# can-SN65HVD233.net
KiCad netlist of a schematic drawn in Altium Designer
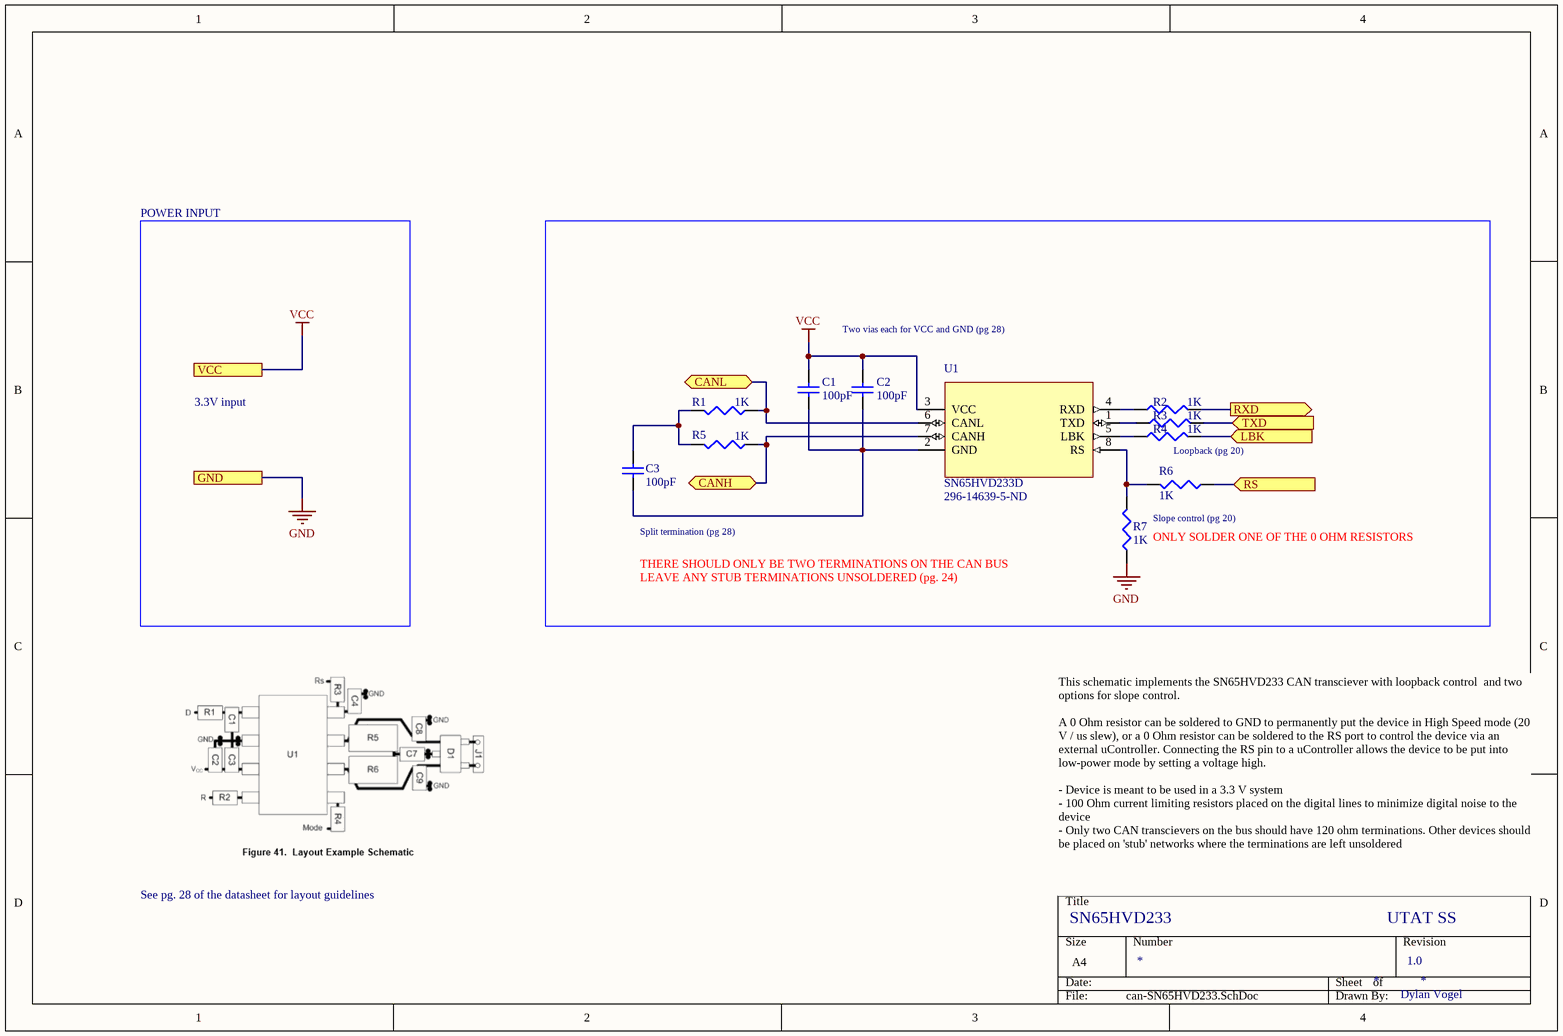
[diagram p0: can-SN65HVD233.SchDoc]

(export (version "E")
  (design (tool "Eeschema 10.0.6"))
  (components
    (comp (ref "C1")
      (value "100pF")
      (footprint "C1206")
      (description "Capacitor (Semiconductor SIM Model)")
      (fields (field (name "Comment") "Cap Semi") (field (name "PUBLISHER") "Altium Limited"))
      (libsource (lib "Miscellaneous Devices") (part "Cap Semi"))
    )
    (comp (ref "C2")
      (value "100pF")
      (footprint "C1206")
      (description "Capacitor (Semiconductor SIM Model)")
      (fields (field (name "Comment") "Cap Semi") (field (name "PUBLISHER") "Altium Limited"))
      (libsource (lib "Miscellaneous Devices") (part "Cap Semi"))
    )
    (comp (ref "C3")
      (value "100pF")
      (footprint "C1206")
      (description "Capacitor (Semiconductor SIM Model)")
      (fields (field (name "Comment") "Cap Semi") (field (name "PUBLISHER") "Altium Limited"))
      (libsource (lib "Miscellaneous Devices") (part "Cap Semi"))
    )
    (comp (ref "R1")
      (value "1K")
      (footprint "J1-0603")
      (description "Resistor")
      (fields (field (name "Comment") "Res3") (field (name "PUBLISHER") "Altium Limited"))
      (libsource (lib "Miscellaneous Devices") (part "Res3"))
    )
    (comp (ref "R2")
      (value "1K")
      (footprint "J1-0603")
      (description "Resistor")
      (fields (field (name "Comment") "Res3") (field (name "PUBLISHER") "Altium Limited"))
      (libsource (lib "Miscellaneous Devices") (part "Res3"))
    )
    (comp (ref "R3")
      (value "1K")
      (footprint "J1-0603")
      (description "Resistor")
      (fields (field (name "Comment") "Res3") (field (name "PUBLISHER") "Altium Limited"))
      (libsource (lib "Miscellaneous Devices") (part "Res3"))
    )
    (comp (ref "R4")
      (value "1K")
      (footprint "J1-0603")
      (description "Resistor")
      (fields (field (name "Comment") "Res3") (field (name "PUBLISHER") "Altium Limited"))
      (libsource (lib "Miscellaneous Devices") (part "Res3"))
    )
    (comp (ref "R5")
      (value "1K")
      (footprint "J1-0603")
      (description "Resistor")
      (fields (field (name "Comment") "Res3") (field (name "PUBLISHER") "Altium Limited"))
      (libsource (lib "Miscellaneous Devices") (part "Res3"))
    )
    (comp (ref "R6")
      (value "1K")
      (footprint "J1-0603")
      (description "Resistor")
      (fields (field (name "Comment") "Res3") (field (name "PUBLISHER") "Altium Limited"))
      (libsource (lib "Miscellaneous Devices") (part "Res3"))
    )
    (comp (ref "R7")
      (value "1K")
      (footprint "J1-0603")
      (description "Resistor")
      (fields (field (name "Comment") "Res3") (field (name "PUBLISHER") "Altium Limited"))
      (libsource (lib "Miscellaneous Devices") (part "Res3"))
    )
    (comp (ref "U1")
      (value "SN65HVD233D")
      (footprint "SOIC127P500X600-8N")
      (description "3.3V CAN Transceiver with Standby Mode, Loop-back 8-SOIC -40 to 125")
      (fields
        (field (name "MF") "Texas Instruments")
        (field (name "SUPPLIER PART NUMBER 1") "296-14639-5-ND")
      )
      (libsource (lib "heron-general") (part "SN65HVD233D"))
    )
  )
  (nets
    (net (code "1") (name "/CANH") (class "Default")
      (node (ref "R5") (pin "1") (pinfunction "1_1") (pintype "passive"))
      (node (ref "U1") (pin "7") (pinfunction "CANH_7") (pintype "bidirectional"))
    )
    (net (code "2") (name "/CANL") (class "Default")
      (node (ref "R1") (pin "1") (pinfunction "1_1") (pintype "passive"))
      (node (ref "U1") (pin "6") (pinfunction "CANL_6") (pintype "bidirectional"))
    )
    (net (code "3") (name "/LBK") (class "Default")
      (node (ref "R4") (pin "2") (pinfunction "2_2") (pintype "passive"))
    )
    (net (code "4") (name "/RS") (class "Default")
      (node (ref "R6") (pin "1") (pinfunction "1_1") (pintype "passive"))
    )
    (net (code "5") (name "/RXD") (class "Default")
      (node (ref "R2") (pin "2") (pinfunction "2_2") (pintype "passive"))
    )
    (net (code "6") (name "/TXD") (class "Default")
      (node (ref "R3") (pin "2") (pinfunction "2_2") (pintype "passive"))
    )
    (net (code "7") (name "GND") (class "Default")
      (node (ref "R7") (pin "1") (pinfunction "1_1") (pintype "passive"))
    )
    (net (code "8") (name "Net-(C3-Pad2)") (class "Default")
      (node (ref "C3") (pin "2") (pinfunction "2_2") (pintype "passive"))
      (node (ref "R1") (pin "2") (pinfunction "2_2") (pintype "passive"))
      (node (ref "R5") (pin "2") (pinfunction "2_2") (pintype "passive"))
    )
    (net (code "9") (name "Net-(U1-GND)") (class "Default")
      (node (ref "C1") (pin "2") (pinfunction "2_2") (pintype "passive"))
      (node (ref "C2") (pin "2") (pinfunction "2_2") (pintype "passive"))
      (node (ref "C3") (pin "1") (pinfunction "1_1") (pintype "passive"))
      (node (ref "U1") (pin "2") (pinfunction "GND_2") (pintype "power_in"))
    )
    (net (code "10") (name "Net-(U1-LBK)") (class "Default")
      (node (ref "R4") (pin "1") (pinfunction "1_1") (pintype "passive"))
      (node (ref "U1") (pin "5") (pinfunction "LBK_5") (pintype "output"))
    )
    (net (code "11") (name "Net-(U1-RS)") (class "Default")
      (node (ref "R6") (pin "2") (pinfunction "2_2") (pintype "passive"))
      (node (ref "R7") (pin "2") (pinfunction "2_2") (pintype "passive"))
      (node (ref "U1") (pin "8") (pinfunction "RS_8") (pintype "input"))
    )
    (net (code "12") (name "Net-(U1-RXD)") (class "Default")
      (node (ref "R2") (pin "1") (pinfunction "1_1") (pintype "passive"))
      (node (ref "U1") (pin "4") (pinfunction "RXD_4") (pintype "output"))
    )
    (net (code "13") (name "Net-(U1-TXD)") (class "Default")
      (node (ref "R3") (pin "1") (pinfunction "1_1") (pintype "passive"))
      (node (ref "U1") (pin "1") (pinfunction "TXD_1") (pintype "bidirectional"))
    )
    (net (code "14") (name "VCC") (class "Default")
      (node (ref "C1") (pin "1") (pinfunction "1_1") (pintype "passive"))
      (node (ref "C2") (pin "1") (pinfunction "1_1") (pintype "passive"))
      (node (ref "U1") (pin "3") (pinfunction "VCC_3") (pintype "power_in"))
    )
  )
)
